# Jukebox_Power.net
KiCad netlist of a schematic drawn in Altium Designer
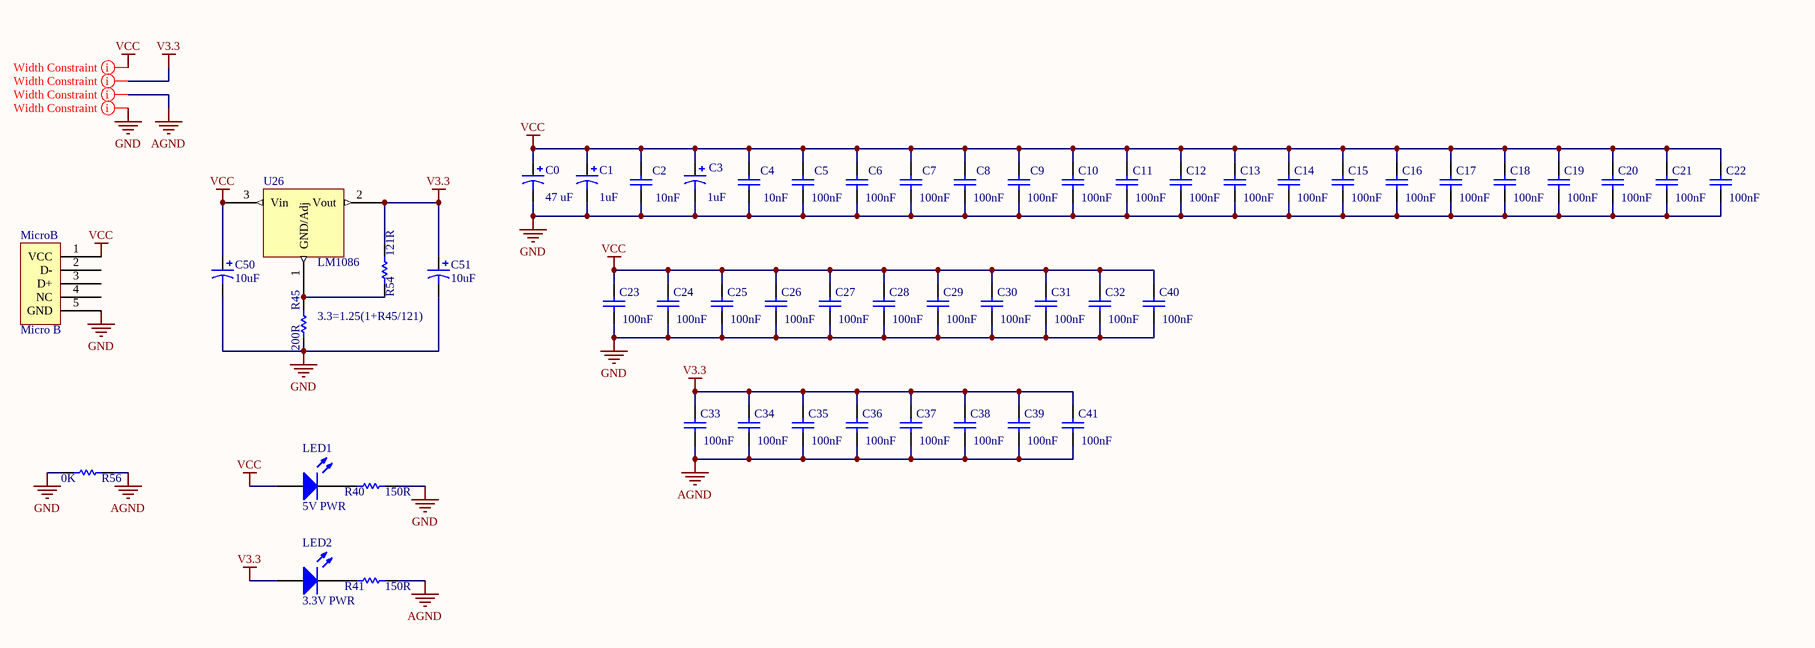
[diagram p0: Jukebox Power.SchDoc]

(export (version "E")
  (design (tool "Eeschema 10.0.6"))
  (components
    (comp (ref "C0")
      (value "47 uF")
      (footprint "RB.1/.2")
      (description "Polarized Capacitor (Surface Mount)")
      (fields (field (name "Comment") "Cap Pol3") (field (name "PUBLISHER") "Altium Limited"))
      (libsource (lib "Miscellaneous Devices") (part "Cap Pol3"))
    )
    (comp (ref "C1")
      (value "1uF")
      (footprint "C0805")
      (description "Polarized Capacitor (Surface Mount)")
      (fields (field (name "Comment") "Cap Pol3") (field (name "PUBLISHER") "Altium Limited"))
      (libsource (lib "Miscellaneous Devices") (part "Cap Pol3"))
    )
    (comp (ref "C2")
      (value "10nF")
      (footprint "C0805")
      (description "Capacitor")
      (fields (field (name "Comment") "Cap") (field (name "PUBLISHER") "Altium Limited"))
      (libsource (lib "Miscellaneous Devices") (part "Cap"))
    )
    (comp (ref "C3")
      (value "1uF")
      (footprint "C0805")
      (description "Polarized Capacitor (Surface Mount)")
      (fields (field (name "Comment") "Cap Pol3") (field (name "PUBLISHER") "Altium Limited"))
      (libsource (lib "Miscellaneous Devices") (part "Cap Pol3"))
    )
    (comp (ref "C4")
      (value "10nF")
      (footprint "C0805")
      (description "Capacitor")
      (fields (field (name "Comment") "Cap") (field (name "PUBLISHER") "Altium Limited"))
      (libsource (lib "Miscellaneous Devices") (part "Cap"))
    )
    (comp (ref "C5")
      (value "100nF")
      (footprint "C0805")
      (description "Capacitor")
      (fields (field (name "Comment") "Cap") (field (name "PUBLISHER") "Altium Limited"))
      (libsource (lib "Miscellaneous Devices") (part "Cap"))
    )
    (comp (ref "C6")
      (value "100nF")
      (footprint "C0805")
      (description "Capacitor")
      (fields (field (name "Comment") "Cap") (field (name "PUBLISHER") "Altium Limited"))
      (libsource (lib "Miscellaneous Devices") (part "Cap"))
    )
    (comp (ref "C7")
      (value "100nF")
      (footprint "C0805")
      (description "Capacitor")
      (fields (field (name "Comment") "Cap") (field (name "PUBLISHER") "Altium Limited"))
      (libsource (lib "Miscellaneous Devices") (part "Cap"))
    )
    (comp (ref "C8")
      (value "100nF")
      (footprint "C0805")
      (description "Capacitor")
      (fields (field (name "Comment") "Cap") (field (name "PUBLISHER") "Altium Limited"))
      (libsource (lib "Miscellaneous Devices") (part "Cap"))
    )
    (comp (ref "C9")
      (value "100nF")
      (footprint "C0805")
      (description "Capacitor")
      (fields (field (name "Comment") "Cap") (field (name "PUBLISHER") "Altium Limited"))
      (libsource (lib "Miscellaneous Devices") (part "Cap"))
    )
    (comp (ref "C10")
      (value "100nF")
      (footprint "C0805")
      (description "Capacitor")
      (fields (field (name "Comment") "Cap") (field (name "PUBLISHER") "Altium Limited"))
      (libsource (lib "Miscellaneous Devices") (part "Cap"))
    )
    (comp (ref "C11")
      (value "100nF")
      (footprint "C0805")
      (description "Capacitor")
      (fields (field (name "Comment") "Cap") (field (name "PUBLISHER") "Altium Limited"))
      (libsource (lib "Miscellaneous Devices") (part "Cap"))
    )
    (comp (ref "C12")
      (value "100nF")
      (footprint "C0805")
      (description "Capacitor")
      (fields (field (name "Comment") "Cap") (field (name "PUBLISHER") "Altium Limited"))
      (libsource (lib "Miscellaneous Devices") (part "Cap"))
    )
    (comp (ref "C13")
      (value "100nF")
      (footprint "C0805")
      (description "Capacitor")
      (fields (field (name "Comment") "Cap") (field (name "PUBLISHER") "Altium Limited"))
      (libsource (lib "Miscellaneous Devices") (part "Cap"))
    )
    (comp (ref "C14")
      (value "100nF")
      (footprint "C0805")
      (description "Capacitor")
      (fields (field (name "Comment") "Cap") (field (name "PUBLISHER") "Altium Limited"))
      (libsource (lib "Miscellaneous Devices") (part "Cap"))
    )
    (comp (ref "C15")
      (value "100nF")
      (footprint "C0805")
      (description "Capacitor")
      (fields (field (name "Comment") "Cap") (field (name "PUBLISHER") "Altium Limited"))
      (libsource (lib "Miscellaneous Devices") (part "Cap"))
    )
    (comp (ref "C16")
      (value "100nF")
      (footprint "C0805")
      (description "Capacitor")
      (fields (field (name "Comment") "Cap") (field (name "PUBLISHER") "Altium Limited"))
      (libsource (lib "Miscellaneous Devices") (part "Cap"))
    )
    (comp (ref "C17")
      (value "100nF")
      (footprint "C0805")
      (description "Capacitor")
      (fields (field (name "Comment") "Cap") (field (name "PUBLISHER") "Altium Limited"))
      (libsource (lib "Miscellaneous Devices") (part "Cap"))
    )
    (comp (ref "C18")
      (value "100nF")
      (footprint "C0805")
      (description "Capacitor")
      (fields (field (name "Comment") "Cap") (field (name "PUBLISHER") "Altium Limited"))
      (libsource (lib "Miscellaneous Devices") (part "Cap"))
    )
    (comp (ref "C19")
      (value "100nF")
      (footprint "C0805")
      (description "Capacitor")
      (fields (field (name "Comment") "Cap") (field (name "PUBLISHER") "Altium Limited"))
      (libsource (lib "Miscellaneous Devices") (part "Cap"))
    )
    (comp (ref "C20")
      (value "100nF")
      (footprint "C0805")
      (description "Capacitor")
      (fields (field (name "Comment") "Cap") (field (name "PUBLISHER") "Altium Limited"))
      (libsource (lib "Miscellaneous Devices") (part "Cap"))
    )
    (comp (ref "C21")
      (value "100nF")
      (footprint "C0805")
      (description "Capacitor")
      (fields (field (name "Comment") "Cap") (field (name "PUBLISHER") "Altium Limited"))
      (libsource (lib "Miscellaneous Devices") (part "Cap"))
    )
    (comp (ref "C22")
      (value "100nF")
      (footprint "C0805")
      (description "Capacitor")
      (fields (field (name "Comment") "Cap") (field (name "PUBLISHER") "Altium Limited"))
      (libsource (lib "Miscellaneous Devices") (part "Cap"))
    )
    (comp (ref "C23")
      (value "100nF")
      (footprint "C0805")
      (description "Capacitor")
      (fields (field (name "Comment") "Cap") (field (name "PUBLISHER") "Altium Limited"))
      (libsource (lib "Miscellaneous Devices") (part "Cap"))
    )
    (comp (ref "C24")
      (value "100nF")
      (footprint "C0805")
      (description "Capacitor")
      (fields (field (name "Comment") "Cap") (field (name "PUBLISHER") "Altium Limited"))
      (libsource (lib "Miscellaneous Devices") (part "Cap"))
    )
    (comp (ref "C25")
      (value "100nF")
      (footprint "C0805")
      (description "Capacitor")
      (fields (field (name "Comment") "Cap") (field (name "PUBLISHER") "Altium Limited"))
      (libsource (lib "Miscellaneous Devices") (part "Cap"))
    )
    (comp (ref "C26")
      (value "100nF")
      (footprint "C0805")
      (description "Capacitor")
      (fields (field (name "Comment") "Cap") (field (name "PUBLISHER") "Altium Limited"))
      (libsource (lib "Miscellaneous Devices") (part "Cap"))
    )
    (comp (ref "C27")
      (value "100nF")
      (footprint "C0805")
      (description "Capacitor")
      (fields (field (name "Comment") "Cap") (field (name "PUBLISHER") "Altium Limited"))
      (libsource (lib "Miscellaneous Devices") (part "Cap"))
    )
    (comp (ref "C28")
      (value "100nF")
      (footprint "C0805")
      (description "Capacitor")
      (fields (field (name "Comment") "Cap") (field (name "PUBLISHER") "Altium Limited"))
      (libsource (lib "Miscellaneous Devices") (part "Cap"))
    )
    (comp (ref "C29")
      (value "100nF")
      (footprint "C0805")
      (description "Capacitor")
      (fields (field (name "Comment") "Cap") (field (name "PUBLISHER") "Altium Limited"))
      (libsource (lib "Miscellaneous Devices") (part "Cap"))
    )
    (comp (ref "C30")
      (value "100nF")
      (footprint "C0805")
      (description "Capacitor")
      (fields (field (name "Comment") "Cap") (field (name "PUBLISHER") "Altium Limited"))
      (libsource (lib "Miscellaneous Devices") (part "Cap"))
    )
    (comp (ref "C31")
      (value "100nF")
      (footprint "C0805")
      (description "Capacitor")
      (fields (field (name "Comment") "Cap") (field (name "PUBLISHER") "Altium Limited"))
      (libsource (lib "Miscellaneous Devices") (part "Cap"))
    )
    (comp (ref "C32")
      (value "100nF")
      (footprint "C0805")
      (description "Capacitor")
      (fields (field (name "Comment") "Cap") (field (name "PUBLISHER") "Altium Limited"))
      (libsource (lib "Miscellaneous Devices") (part "Cap"))
    )
    (comp (ref "C33")
      (value "100nF")
      (footprint "C0805")
      (description "Capacitor")
      (fields (field (name "Comment") "Cap") (field (name "PUBLISHER") "Altium Limited"))
      (libsource (lib "Miscellaneous Devices") (part "Cap"))
    )
    (comp (ref "C34")
      (value "100nF")
      (footprint "C0805")
      (description "Capacitor")
      (fields (field (name "Comment") "Cap") (field (name "PUBLISHER") "Altium Limited"))
      (libsource (lib "Miscellaneous Devices") (part "Cap"))
    )
    (comp (ref "C35")
      (value "100nF")
      (footprint "C0805")
      (description "Capacitor")
      (fields (field (name "Comment") "Cap") (field (name "PUBLISHER") "Altium Limited"))
      (libsource (lib "Miscellaneous Devices") (part "Cap"))
    )
    (comp (ref "C36")
      (value "100nF")
      (footprint "C0805")
      (description "Capacitor")
      (fields (field (name "Comment") "Cap") (field (name "PUBLISHER") "Altium Limited"))
      (libsource (lib "Miscellaneous Devices") (part "Cap"))
    )
    (comp (ref "C37")
      (value "100nF")
      (footprint "C0805")
      (description "Capacitor")
      (fields (field (name "Comment") "Cap") (field (name "PUBLISHER") "Altium Limited"))
      (libsource (lib "Miscellaneous Devices") (part "Cap"))
    )
    (comp (ref "C38")
      (value "100nF")
      (footprint "C0805")
      (description "Capacitor")
      (fields (field (name "Comment") "Cap") (field (name "PUBLISHER") "Altium Limited"))
      (libsource (lib "Miscellaneous Devices") (part "Cap"))
    )
    (comp (ref "C39")
      (value "100nF")
      (footprint "C0805")
      (description "Capacitor")
      (fields (field (name "Comment") "Cap") (field (name "PUBLISHER") "Altium Limited"))
      (libsource (lib "Miscellaneous Devices") (part "Cap"))
    )
    (comp (ref "C40")
      (value "100nF")
      (footprint "C0805")
      (description "Capacitor")
      (fields (field (name "Comment") "Cap") (field (name "PUBLISHER") "Altium Limited"))
      (libsource (lib "Miscellaneous Devices") (part "Cap"))
    )
    (comp (ref "C41")
      (value "100nF")
      (footprint "C0805")
      (description "Capacitor")
      (fields (field (name "Comment") "Cap") (field (name "PUBLISHER") "Altium Limited"))
      (libsource (lib "Miscellaneous Devices") (part "Cap"))
    )
    (comp (ref "C50")
      (value "10uF")
      (footprint "C0805")
      (description "Polarized Capacitor (Surface Mount)")
      (fields (field (name "Comment") "Cap Pol3") (field (name "PUBLISHER") "Altium Limited"))
      (libsource (lib "Miscellaneous Devices") (part "Cap Pol3"))
    )
    (comp (ref "C51")
      (value "10uF")
      (footprint "C0805")
      (description "Polarized Capacitor (Surface Mount)")
      (fields (field (name "Comment") "Cap Pol3") (field (name "PUBLISHER") "Altium Limited"))
      (libsource (lib "Miscellaneous Devices") (part "Cap Pol3"))
    )
    (comp (ref "LED1")
      (value "5V PWR")
      (footprint "3.2X1.6X1.1")
      (description "Typical RED, GREEN, YELLOW, AMBER GaAs LED")
      (fields (field (name "PUBLISHER") "Altium Limited"))
      (libsource (lib "Miscellaneous Devices") (part "LED2"))
    )
    (comp (ref "LED2")
      (value "3.3V PWR")
      (footprint "3.2X1.6X1.1")
      (description "Typical RED, GREEN, YELLOW, AMBER GaAs LED")
      (fields (field (name "PUBLISHER") "Altium Limited"))
      (libsource (lib "Miscellaneous Devices") (part "LED2"))
    )
    (comp (ref "MicroB")
      (value "Micro B")
      (footprint "10118192")
      (libsource (lib "eecs52_Tim") (part "10118192 Micro B USB"))
    )
    (comp (ref "R40")
      (value "150R")
      (footprint "6-0805_L")
      (description "Resistor")
      (fields (field (name "Comment") "Res1") (field (name "PUBLISHER") "Altium Limited"))
      (libsource (lib "Miscellaneous Devices") (part "Res1"))
    )
    (comp (ref "R41")
      (value "150R")
      (footprint "6-0805_L")
      (description "Resistor")
      (fields (field (name "Comment") "Res1") (field (name "PUBLISHER") "Altium Limited"))
      (libsource (lib "Miscellaneous Devices") (part "Res1"))
    )
    (comp (ref "R45")
      (value "200R")
      (footprint "6-0805_L")
      (description "Resistor")
      (fields (field (name "Comment") "Res1") (field (name "PUBLISHER") "Altium Limited"))
      (libsource (lib "Miscellaneous Devices") (part "Res1"))
    )
    (comp (ref "R54")
      (value "121R")
      (footprint "6-0805_L")
      (description "Resistor")
      (fields (field (name "Comment") "Res1") (field (name "PUBLISHER") "Altium Limited"))
      (libsource (lib "Miscellaneous Devices") (part "Res1"))
    )
    (comp (ref "R56")
      (value "0K")
      (footprint "6-0805_L")
      (description "Resistor")
      (fields (field (name "Comment") "Res1") (field (name "PUBLISHER") "Altium Limited"))
      (libsource (lib "Miscellaneous Devices") (part "Res1"))
    )
    (comp (ref "U26")
      (value "LM1086")
      (footprint "TO-220")
      (description "1.5A Low Dropout Positive Regulator")
      (libsource (lib "eecs5x") (part "LM1086"))
    )
  )
  (nets
    (net (code "1") (name "AGND") (class "Default")
      (node (ref "C33") (pin "1") (pinfunction "1_1") (pintype "passive"))
      (node (ref "C34") (pin "1") (pinfunction "1_1") (pintype "passive"))
      (node (ref "C35") (pin "1") (pinfunction "1_1") (pintype "passive"))
      (node (ref "C36") (pin "1") (pinfunction "1_1") (pintype "passive"))
      (node (ref "C37") (pin "1") (pinfunction "1_1") (pintype "passive"))
      (node (ref "C38") (pin "1") (pinfunction "1_1") (pintype "passive"))
      (node (ref "C39") (pin "1") (pinfunction "1_1") (pintype "passive"))
      (node (ref "C41") (pin "1") (pinfunction "1_1") (pintype "passive"))
      (node (ref "R41") (pin "1") (pinfunction "1_1") (pintype "passive"))
      (node (ref "R56") (pin "1") (pinfunction "1_1") (pintype "passive"))
    )
    (net (code "2") (name "GND") (class "Default")
      (node (ref "C0") (pin "2") (pinfunction "2_2") (pintype "passive"))
      (node (ref "C1") (pin "2") (pinfunction "2_2") (pintype "passive"))
      (node (ref "C10") (pin "1") (pinfunction "1_1") (pintype "passive"))
      (node (ref "C11") (pin "1") (pinfunction "1_1") (pintype "passive"))
      (node (ref "C12") (pin "1") (pinfunction "1_1") (pintype "passive"))
      (node (ref "C13") (pin "1") (pinfunction "1_1") (pintype "passive"))
      (node (ref "C14") (pin "1") (pinfunction "1_1") (pintype "passive"))
      (node (ref "C15") (pin "1") (pinfunction "1_1") (pintype "passive"))
      (node (ref "C16") (pin "1") (pinfunction "1_1") (pintype "passive"))
      (node (ref "C17") (pin "1") (pinfunction "1_1") (pintype "passive"))
      (node (ref "C18") (pin "1") (pinfunction "1_1") (pintype "passive"))
      (node (ref "C19") (pin "1") (pinfunction "1_1") (pintype "passive"))
      (node (ref "C2") (pin "1") (pinfunction "1_1") (pintype "passive"))
      (node (ref "C20") (pin "1") (pinfunction "1_1") (pintype "passive"))
      (node (ref "C21") (pin "1") (pinfunction "1_1") (pintype "passive"))
      (node (ref "C22") (pin "1") (pinfunction "1_1") (pintype "passive"))
      (node (ref "C23") (pin "1") (pinfunction "1_1") (pintype "passive"))
      (node (ref "C24") (pin "1") (pinfunction "1_1") (pintype "passive"))
      (node (ref "C25") (pin "1") (pinfunction "1_1") (pintype "passive"))
      (node (ref "C26") (pin "1") (pinfunction "1_1") (pintype "passive"))
      (node (ref "C27") (pin "1") (pinfunction "1_1") (pintype "passive"))
      (node (ref "C28") (pin "1") (pinfunction "1_1") (pintype "passive"))
      (node (ref "C29") (pin "1") (pinfunction "1_1") (pintype "passive"))
      (node (ref "C3") (pin "2") (pinfunction "2_2") (pintype "passive"))
      (node (ref "C30") (pin "1") (pinfunction "1_1") (pintype "passive"))
      (node (ref "C31") (pin "1") (pinfunction "1_1") (pintype "passive"))
      (node (ref "C32") (pin "1") (pinfunction "1_1") (pintype "passive"))
      (node (ref "C4") (pin "1") (pinfunction "1_1") (pintype "passive"))
      (node (ref "C40") (pin "1") (pinfunction "1_1") (pintype "passive"))
      (node (ref "C5") (pin "1") (pinfunction "1_1") (pintype "passive"))
      (node (ref "C50") (pin "2") (pinfunction "2_2") (pintype "passive"))
      (node (ref "C51") (pin "2") (pinfunction "2_2") (pintype "passive"))
      (node (ref "C6") (pin "1") (pinfunction "1_1") (pintype "passive"))
      (node (ref "C7") (pin "1") (pinfunction "1_1") (pintype "passive"))
      (node (ref "C8") (pin "1") (pinfunction "1_1") (pintype "passive"))
      (node (ref "C9") (pin "1") (pinfunction "1_1") (pintype "passive"))
      (node (ref "MicroB") (pin "5") (pinfunction "GND_5") (pintype "passive"))
      (node (ref "R40") (pin "1") (pinfunction "1_1") (pintype "passive"))
      (node (ref "R45") (pin "2") (pinfunction "2_2") (pintype "passive"))
      (node (ref "R56") (pin "2") (pinfunction "2_2") (pintype "passive"))
    )
    (net (code "3") (name "Net-(LED1-K)") (class "Default")
      (node (ref "LED1") (pin "2") (pinfunction "K_2") (pintype "passive"))
      (node (ref "R40") (pin "2") (pinfunction "2_2") (pintype "passive"))
    )
    (net (code "4") (name "Net-(LED2-K)") (class "Default")
      (node (ref "LED2") (pin "2") (pinfunction "K_2") (pintype "passive"))
      (node (ref "R41") (pin "2") (pinfunction "2_2") (pintype "passive"))
    )
    (net (code "5") (name "Net-(U26-GND{slash}Adj)") (class "Default")
      (node (ref "R45") (pin "1") (pinfunction "1_1") (pintype "passive"))
      (node (ref "R54") (pin "1") (pinfunction "1_1") (pintype "passive"))
      (node (ref "U26") (pin "1") (pinfunction "GND/Adj_1") (pintype "output"))
    )
    (net (code "6") (name "V3.3") (class "Default")
      (node (ref "C33") (pin "2") (pinfunction "2_2") (pintype "passive"))
      (node (ref "C34") (pin "2") (pinfunction "2_2") (pintype "passive"))
      (node (ref "C35") (pin "2") (pinfunction "2_2") (pintype "passive"))
      (node (ref "C36") (pin "2") (pinfunction "2_2") (pintype "passive"))
      (node (ref "C37") (pin "2") (pinfunction "2_2") (pintype "passive"))
      (node (ref "C38") (pin "2") (pinfunction "2_2") (pintype "passive"))
      (node (ref "C39") (pin "2") (pinfunction "2_2") (pintype "passive"))
      (node (ref "C41") (pin "2") (pinfunction "2_2") (pintype "passive"))
      (node (ref "C51") (pin "1") (pinfunction "1_1") (pintype "passive"))
      (node (ref "LED2") (pin "1") (pinfunction "A_1") (pintype "passive"))
      (node (ref "R54") (pin "2") (pinfunction "2_2") (pintype "passive"))
      (node (ref "U26") (pin "2") (pinfunction "Vout_2") (pintype "output"))
    )
    (net (code "7") (name "VCC") (class "Default")
      (node (ref "C0") (pin "1") (pinfunction "1_1") (pintype "passive"))
      (node (ref "C1") (pin "1") (pinfunction "1_1") (pintype "passive"))
      (node (ref "C10") (pin "2") (pinfunction "2_2") (pintype "passive"))
      (node (ref "C11") (pin "2") (pinfunction "2_2") (pintype "passive"))
      (node (ref "C12") (pin "2") (pinfunction "2_2") (pintype "passive"))
      (node (ref "C13") (pin "2") (pinfunction "2_2") (pintype "passive"))
      (node (ref "C14") (pin "2") (pinfunction "2_2") (pintype "passive"))
      (node (ref "C15") (pin "2") (pinfunction "2_2") (pintype "passive"))
      (node (ref "C16") (pin "2") (pinfunction "2_2") (pintype "passive"))
      (node (ref "C17") (pin "2") (pinfunction "2_2") (pintype "passive"))
      (node (ref "C18") (pin "2") (pinfunction "2_2") (pintype "passive"))
      (node (ref "C19") (pin "2") (pinfunction "2_2") (pintype "passive"))
      (node (ref "C2") (pin "2") (pinfunction "2_2") (pintype "passive"))
      (node (ref "C20") (pin "2") (pinfunction "2_2") (pintype "passive"))
      (node (ref "C21") (pin "2") (pinfunction "2_2") (pintype "passive"))
      (node (ref "C22") (pin "2") (pinfunction "2_2") (pintype "passive"))
      (node (ref "C23") (pin "2") (pinfunction "2_2") (pintype "passive"))
      (node (ref "C24") (pin "2") (pinfunction "2_2") (pintype "passive"))
      (node (ref "C25") (pin "2") (pinfunction "2_2") (pintype "passive"))
      (node (ref "C26") (pin "2") (pinfunction "2_2") (pintype "passive"))
      (node (ref "C27") (pin "2") (pinfunction "2_2") (pintype "passive"))
      (node (ref "C28") (pin "2") (pinfunction "2_2") (pintype "passive"))
      (node (ref "C29") (pin "2") (pinfunction "2_2") (pintype "passive"))
      (node (ref "C3") (pin "1") (pinfunction "1_1") (pintype "passive"))
      (node (ref "C30") (pin "2") (pinfunction "2_2") (pintype "passive"))
      (node (ref "C31") (pin "2") (pinfunction "2_2") (pintype "passive"))
      (node (ref "C32") (pin "2") (pinfunction "2_2") (pintype "passive"))
      (node (ref "C4") (pin "2") (pinfunction "2_2") (pintype "passive"))
      (node (ref "C40") (pin "2") (pinfunction "2_2") (pintype "passive"))
      (node (ref "C5") (pin "2") (pinfunction "2_2") (pintype "passive"))
      (node (ref "C50") (pin "1") (pinfunction "1_1") (pintype "passive"))
      (node (ref "C6") (pin "2") (pinfunction "2_2") (pintype "passive"))
      (node (ref "C7") (pin "2") (pinfunction "2_2") (pintype "passive"))
      (node (ref "C8") (pin "2") (pinfunction "2_2") (pintype "passive"))
      (node (ref "C9") (pin "2") (pinfunction "2_2") (pintype "passive"))
      (node (ref "LED1") (pin "1") (pinfunction "A_1") (pintype "passive"))
      (node (ref "MicroB") (pin "1") (pinfunction "VCC_1") (pintype "passive"))
      (node (ref "U26") (pin "3") (pinfunction "Vin_3") (pintype "output"))
    )
    (net (code "8") (name "unconnected-(MicroB-D+-Pad3)") (class "Default")
      (node (ref "MicroB") (pin "3") (pinfunction "D+_3") (pintype "passive"))
    )
    (net (code "9") (name "unconnected-(MicroB-D--Pad2)") (class "Default")
      (node (ref "MicroB") (pin "2") (pinfunction "D-_2") (pintype "passive"))
    )
    (net (code "10") (name "unconnected-(MicroB-NC-Pad4)") (class "Default")
      (node (ref "MicroB") (pin "4") (pinfunction "NC_4") (pintype "passive"))
    )
  )
)
